# inverter.net
KiCad netlist of a schematic drawn in Altium Designer
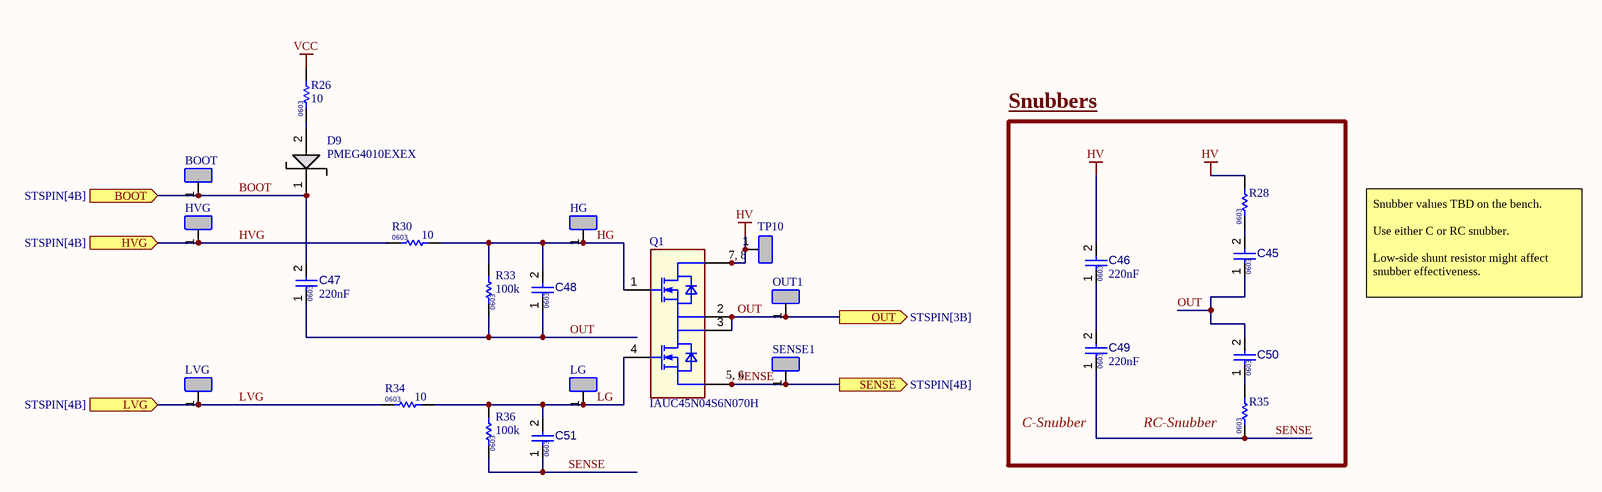
[diagram p0: inverter.SchDoc]

(export (version "E")
  (design (tool "Eeschema 10.0.6"))
  (components
    (comp (ref "BOOT")
      (value "RCT-0C")
      (footprint "RCT-0C-Footprint-1")
      (description "Metal Foil, 0W, 0.05ohm, Surface Mount, 0805")
      (libsource (lib "UBC Thunderbots") (part "RCT-0C"))
    )
    (comp (ref "C45")
      (value "Ceramic Capacitor 0603 Temp")
      (footprint "0603 IPC Class B")
      (description "Template for 0603 ceramic capacitor")
      (libsource (lib "UBC Thunderbots") (part "CAP-NP-2"))
    )
    (comp (ref "C46")
      (value "220nF")
      (footprint "0603 IPC Class B")
      (fields (field (name "Comment") "Ceramic Capacitor 0.22uF +/-10% 50V 0603"))
      (libsource (lib "UBC Thunderbots") (part "CAP-NP-2"))
    )
    (comp (ref "C47")
      (value "220nF")
      (footprint "0603 IPC Class B")
      (fields (field (name "Comment") "Ceramic Capacitor 0.22uF +/-10% 50V 0603"))
      (libsource (lib "UBC Thunderbots") (part "CAP-NP-2"))
    )
    (comp (ref "C48")
      (value "Ceramic Capacitor 0603 Temp")
      (footprint "0603 IPC Class B")
      (description "Template for 0603 ceramic capacitor")
      (libsource (lib "UBC Thunderbots") (part "CAP-NP-2"))
    )
    (comp (ref "C49")
      (value "220nF")
      (footprint "0603 IPC Class B")
      (fields (field (name "Comment") "Ceramic Capacitor 0.22uF +/-10% 50V 0603"))
      (libsource (lib "UBC Thunderbots") (part "CAP-NP-2"))
    )
    (comp (ref "C50")
      (value "Ceramic Capacitor 0603 Temp")
      (footprint "0603 IPC Class B")
      (description "Template for 0603 ceramic capacitor")
      (libsource (lib "UBC Thunderbots") (part "CAP-NP-2"))
    )
    (comp (ref "C51")
      (value "Ceramic Capacitor 0603 Temp")
      (footprint "0603 IPC Class B")
      (description "Template for 0603 ceramic capacitor")
      (libsource (lib "UBC Thunderbots") (part "CAP-NP-2"))
    )
    (comp (ref "D9")
      (value "PMEG4010EXEX")
      (footprint "PMEG4010EXEX")
      (description "PMEG4010EXE-Q - 40 V")
      (libsource (lib "UBC Thunderbots") (part "PMEG4010EXEX"))
    )
    (comp (ref "HG")
      (value "RCT-0C")
      (footprint "RCT-0C-Footprint-1")
      (description "Metal Foil, 0W, 0.05ohm, Surface Mount, 0805")
      (libsource (lib "UBC Thunderbots") (part "RCT-0C"))
    )
    (comp (ref "HVG")
      (value "RCT-0C")
      (footprint "RCT-0C-Footprint-1")
      (description "Metal Foil, 0W, 0.05ohm, Surface Mount, 0805")
      (libsource (lib "UBC Thunderbots") (part "RCT-0C"))
    )
    (comp (ref "LG")
      (value "RCT-0C")
      (footprint "RCT-0C-Footprint-1")
      (description "Metal Foil, 0W, 0.05ohm, Surface Mount, 0805")
      (libsource (lib "UBC Thunderbots") (part "RCT-0C"))
    )
    (comp (ref "LVG")
      (value "RCT-0C")
      (footprint "RCT-0C-Footprint-1")
      (description "Metal Foil, 0W, 0.05ohm, Surface Mount, 0805")
      (libsource (lib "UBC Thunderbots") (part "RCT-0C"))
    )
    (comp (ref "OUT1")
      (value "RCT-0C")
      (footprint "RCT-0C-Footprint-1")
      (description "Metal Foil, 0W, 0.05ohm, Surface Mount, 0805")
      (libsource (lib "UBC Thunderbots") (part "RCT-0C"))
    )
    (comp (ref "Q1")
      (value "IAUC45N04S6N070H")
      (footprint "IFX-PG-TDSON-8-57-V")
      (description "MOSFET 2N-CH 40V 45A 8TDSON")
      (fields (field (name "MANUFACTURER") "Infineon Technologies"))
      (libsource (lib "MDV6-TEMP") (part "IAUC45N04S6N070H"))
    )
    (comp (ref "R26")
      (value "10")
      (footprint "0603 IPC Class B")
      (description "SMD Chip Resistor, 10 Ohm, ± 1%, 250 mW, 0603 [1608 Metric], Thick Film, Anti-Surge")
      (fields (field (name "POWER") "250mW") (field (name "Comment") "Resistor 10R +/-1% 250mW 0603"))
      (libsource (lib "UBC Thunderbots") (part "RES-2"))
    )
    (comp (ref "R28")
      (value "Resistor 0603 Temp")
      (footprint "0603 IPC Class B")
      (description "Template for 0603 Resistor")
      (libsource (lib "UBC Thunderbots") (part "RES-2"))
    )
    (comp (ref "R30")
      (value "10")
      (footprint "0603 IPC Class B")
      (description "SMD Chip Resistor, 10 Ohm, ± 1%, 250 mW, 0603 [1608 Metric], Thick Film, Anti-Surge")
      (fields (field (name "POWER") "250mW") (field (name "Comment") "Resistor 10R +/-1% 250mW 0603"))
      (libsource (lib "UBC Thunderbots") (part "RES-2"))
    )
    (comp (ref "R33")
      (value "100k")
      (footprint "0603 IPC Class B")
      (fields
        (field (name "TOLERANCE") "1%")
        (field (name "POWER") "100mW")
        (field (name "Comment") "Resistor 100k +/-1% 1/10W 0603")
      )
      (libsource (lib "") (part "RES-2_1"))
    )
    (comp (ref "R34")
      (value "10")
      (footprint "0603 IPC Class B")
      (description "SMD Chip Resistor, 10 Ohm, ± 1%, 250 mW, 0603 [1608 Metric], Thick Film, Anti-Surge")
      (fields (field (name "POWER") "250mW") (field (name "Comment") "Resistor 10R +/-1% 250mW 0603"))
      (libsource (lib "UBC Thunderbots") (part "RES-2"))
    )
    (comp (ref "R35")
      (value "Resistor 0603 Temp")
      (footprint "0603 IPC Class B")
      (description "Template for 0603 Resistor")
      (libsource (lib "UBC Thunderbots") (part "RES-2"))
    )
    (comp (ref "R36")
      (value "100k")
      (footprint "0603 IPC Class B")
      (fields
        (field (name "TOLERANCE") "1%")
        (field (name "POWER") "100mW")
        (field (name "Comment") "Resistor 100k +/-1% 1/10W 0603")
      )
      (libsource (lib "") (part "RES-2_1"))
    )
    (comp (ref "SENSE1")
      (value "RCT-0C")
      (footprint "RCT-0C-Footprint-1")
      (description "Metal Foil, 0W, 0.05ohm, Surface Mount, 0805")
      (libsource (lib "UBC Thunderbots") (part "RCT-0C"))
    )
    (comp (ref "TP10")
      (value "RCT-0C")
      (footprint "RCT-0C-Footprint-1")
      (description "Metal Foil, 0W, 0.05ohm, Surface Mount, 0805")
      (libsource (lib "UBC Thunderbots") (part "RCT-0C"))
    )
  )
  (nets
    (net (code "1") (name "/BOOT") (class "Default")
      (node (ref "BOOT") (pin "1") (pinfunction "SIGNAL_1") (pintype "passive"))
      (node (ref "C47") (pin "2") (pinfunction "2_2") (pintype "passive"))
      (node (ref "D9") (pin "1") (pinfunction "K_1") (pintype "passive"))
    )
    (net (code "2") (name "/HG") (class "Default")
      (node (ref "C48") (pin "2") (pinfunction "2_2") (pintype "passive"))
      (node (ref "HG") (pin "1") (pinfunction "SIGNAL_1") (pintype "passive"))
      (node (ref "Q1") (pin "1") (pinfunction "GATE1_1") (pintype "passive"))
      (node (ref "R30") (pin "2") (pinfunction "2_2") (pintype "passive"))
      (node (ref "R33") (pin "2") (pinfunction "2_2") (pintype "passive"))
    )
    (net (code "3") (name "/HVG") (class "Default")
      (node (ref "HVG") (pin "1") (pinfunction "SIGNAL_1") (pintype "passive"))
      (node (ref "R30") (pin "1") (pinfunction "1_1") (pintype "passive"))
    )
    (net (code "4") (name "/LG") (class "Default")
      (node (ref "C51") (pin "2") (pinfunction "2_2") (pintype "passive"))
      (node (ref "LG") (pin "1") (pinfunction "SIGNAL_1") (pintype "passive"))
      (node (ref "Q1") (pin "4") (pinfunction "GATE2_4") (pintype "passive"))
      (node (ref "R34") (pin "2") (pinfunction "2_2") (pintype "passive"))
      (node (ref "R36") (pin "2") (pinfunction "2_2") (pintype "passive"))
    )
    (net (code "5") (name "/LVG") (class "Default")
      (node (ref "LVG") (pin "1") (pinfunction "SIGNAL_1") (pintype "passive"))
      (node (ref "R34") (pin "1") (pinfunction "1_1") (pintype "passive"))
    )
    (net (code "6") (name "/OUT") (class "Default")
      (node (ref "C45") (pin "1") (pinfunction "1_1") (pintype "passive"))
      (node (ref "C47") (pin "1") (pinfunction "1_1") (pintype "passive"))
      (node (ref "C48") (pin "1") (pinfunction "1_1") (pintype "passive"))
      (node (ref "C50") (pin "2") (pinfunction "2_2") (pintype "passive"))
      (node (ref "OUT1") (pin "1") (pinfunction "SIGNAL_1") (pintype "passive"))
      (node (ref "Q1") (pin "2") (pinfunction "SOURCE1_2") (pintype "passive"))
      (node (ref "Q1") (pin "3") (pinfunction "DRAIN2_3") (pintype "passive"))
      (node (ref "R33") (pin "1") (pinfunction "1_1") (pintype "passive"))
    )
    (net (code "7") (name "/SENSE") (class "Default")
      (node (ref "C49") (pin "1") (pinfunction "1_1") (pintype "passive"))
      (node (ref "C51") (pin "1") (pinfunction "1_1") (pintype "passive"))
      (node (ref "Q1") (pin "5") (pinfunction "SOURCE2_1_5") (pintype "passive"))
      (node (ref "Q1") (pin "6") (pinfunction "SOURCE2_2_6") (pintype "passive"))
      (node (ref "R35") (pin "1") (pinfunction "1_1") (pintype "passive"))
      (node (ref "R36") (pin "1") (pinfunction "1_1") (pintype "passive"))
      (node (ref "SENSE1") (pin "1") (pinfunction "SIGNAL_1") (pintype "passive"))
    )
    (net (code "8") (name "HV") (class "Default")
      (node (ref "C46") (pin "2") (pinfunction "2_2") (pintype "passive"))
      (node (ref "Q1") (pin "7") (pinfunction "DRAIN1_1_7") (pintype "passive"))
      (node (ref "Q1") (pin "8") (pinfunction "DRAIN1_2_8") (pintype "passive"))
      (node (ref "R28") (pin "2") (pinfunction "2_2") (pintype "passive"))
      (node (ref "TP10") (pin "1") (pinfunction "SIGNAL_1") (pintype "passive"))
    )
    (net (code "9") (name "Net-(C45-Pad2)") (class "Default")
      (node (ref "C45") (pin "2") (pinfunction "2_2") (pintype "passive"))
      (node (ref "R28") (pin "1") (pinfunction "1_1") (pintype "passive"))
    )
    (net (code "10") (name "Net-(C46-Pad1)") (class "Default")
      (node (ref "C46") (pin "1") (pinfunction "1_1") (pintype "passive"))
      (node (ref "C49") (pin "2") (pinfunction "2_2") (pintype "passive"))
    )
    (net (code "11") (name "Net-(C50-Pad1)") (class "Default")
      (node (ref "C50") (pin "1") (pinfunction "1_1") (pintype "passive"))
      (node (ref "R35") (pin "2") (pinfunction "2_2") (pintype "passive"))
    )
    (net (code "12") (name "Net-(D9-A)") (class "Default")
      (node (ref "D9") (pin "2") (pinfunction "A_2") (pintype "passive"))
      (node (ref "R26") (pin "1") (pinfunction "1_1") (pintype "passive"))
    )
    (net (code "13") (name "VCC") (class "Default")
      (node (ref "R26") (pin "2") (pinfunction "2_2") (pintype "passive"))
    )
  )
)
